# io9.net
KiCad netlist of a schematic drawn in Altium Designer
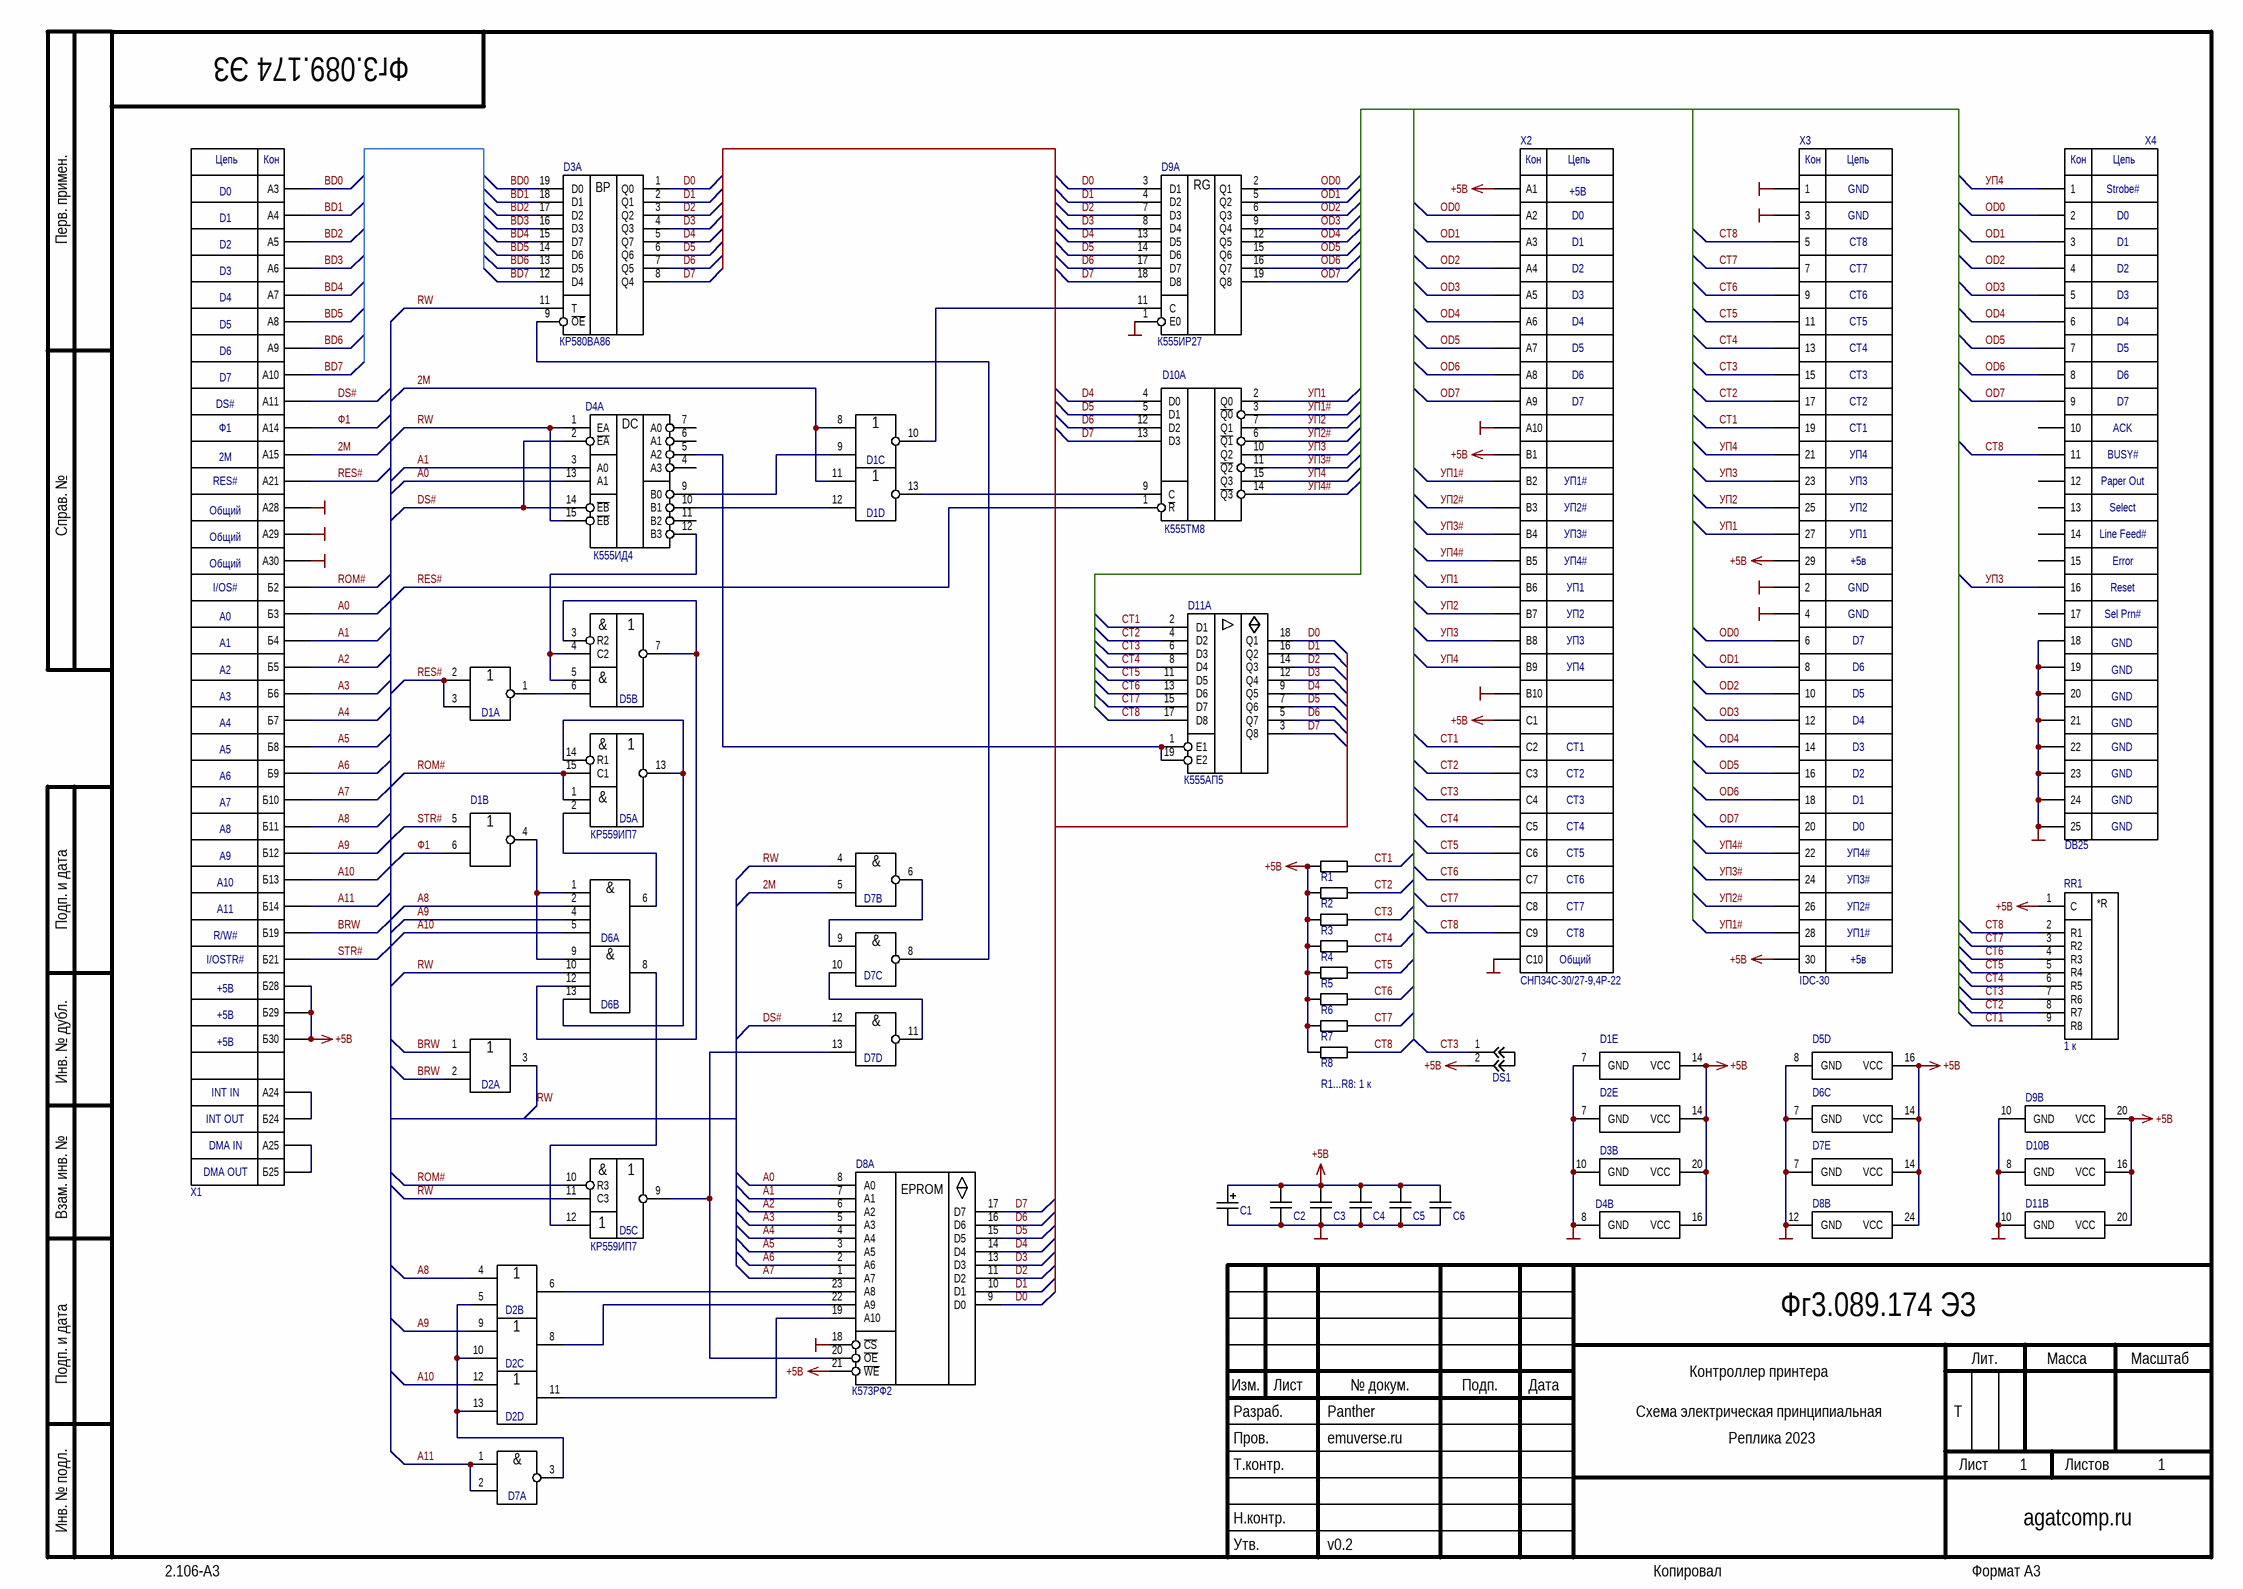
[diagram p0: io9.SchDoc]

(export (version "E")
  (design (tool "Eeschema 10.0.6"))
  (components
    (comp (ref "C1")
      (value "47,0 х 16 в")
      (footprint "CP30")
      (description "К53-14")
      (libsource (lib "Agat") (part "К53-14"))
    )
    (comp (ref "C2")
      (value "0,1 мкф")
      (footprint "C5")
      (description "К10-17")
      (libsource (lib "Agat") (part "К10-17"))
    )
    (comp (ref "C3")
      (value "0,1 мкф")
      (footprint "C5")
      (description "К10-17")
      (libsource (lib "Agat") (part "К10-17"))
    )
    (comp (ref "C4")
      (value "0,1 мкф")
      (footprint "C5")
      (description "К10-17")
      (libsource (lib "Agat") (part "К10-17"))
    )
    (comp (ref "C5")
      (value "0,1 мкф")
      (footprint "C5")
      (description "К10-17")
      (libsource (lib "Agat") (part "К10-17"))
    )
    (comp (ref "C6")
      (value "0,1 мкф")
      (footprint "C5")
      (description "К10-17")
      (libsource (lib "Agat") (part "К10-17"))
    )
    (comp (ref "D1")
      (value "К555ЛЕ1")
      (footprint "201.14")
      (fields (field (name "MANUFACTURERPARTNUMBER") "К555ЛА3"))
      (libsource (lib "Agat") (part "К555ЛЕ1"))
    )
    (comp (ref "D2")
      (value "К555ЛЛ1")
      (footprint "201.14")
      (fields (field (name "MANUFACTURERPARTNUMBER") "К555ЛА3"))
      (libsource (lib "Agat") (part "К555ЛЛ1"))
    )
    (comp (ref "D3") (value "КР580ВА86") (footprint "2140.20") (libsource (lib "Agat") (part "КР580ВА86")))
    (comp (ref "D4") (value "К555ИД4") (footprint "201.16") (libsource (lib "Agat") (part "К555ИД4")))
    (comp (ref "D5")
      (value "КР559ИП7")
      (footprint "201.16")
      (fields (field (name "MANUFACTURERPARTNUMBER") "К555ЛА3"))
      (libsource (lib "Agat") (part "КР559ИП7"))
    )
    (comp (ref "D6")
      (value "К555ЛИ6")
      (footprint "201.14")
      (fields (field (name "MANUFACTURERPARTNUMBER") "К555ЛА3"))
      (libsource (lib "Agat") (part "К555ЛИ6"))
    )
    (comp (ref "D7") (value "К555ЛА3") (footprint "201.14") (libsource (lib "Agat") (part "К555ЛА3")))
    (comp (ref "D8") (value "К573РФ2") (footprint "2120.24 socket") (libsource (lib "Agat") (part "К573РФ2")))
    (comp (ref "D9") (value "К555ИР27") (footprint "201.20") (libsource (lib "Agat") (part "К555ИР27")))
    (comp (ref "D10") (value "К555ТМ8") (footprint "201.16") (libsource (lib "Agat") (part "К555ТМ8")))
    (comp (ref "D11") (value "К555АП5") (footprint "201.20") (libsource (lib "Agat") (part "К555АП5")))
    (comp (ref "DS1")
      (value "HEADER_2x1")
      (footprint "HEADER_2x1")
      (libsource (lib "Agat") (part "HEADER_2x1"))
    )
    (comp (ref "R1")
      (value "1 к")
      (footprint "R10")
      (description "Резистор")
      (libsource (lib "Agat") (part "С2-23"))
    )
    (comp (ref "R2")
      (value "1 к")
      (footprint "R10")
      (description "Резистор")
      (libsource (lib "Agat") (part "С2-23"))
    )
    (comp (ref "R3")
      (value "1 к")
      (footprint "R10")
      (description "Резистор")
      (libsource (lib "Agat") (part "С2-23"))
    )
    (comp (ref "R4")
      (value "1 к")
      (footprint "R10")
      (description "Резистор")
      (libsource (lib "Agat") (part "С2-23"))
    )
    (comp (ref "R5")
      (value "1 к")
      (footprint "R10")
      (description "Резистор")
      (libsource (lib "Agat") (part "С2-23"))
    )
    (comp (ref "R6")
      (value "1 к")
      (footprint "R10")
      (description "Резистор")
      (libsource (lib "Agat") (part "С2-23"))
    )
    (comp (ref "R7")
      (value "1 к")
      (footprint "R10")
      (description "Резистор")
      (libsource (lib "Agat") (part "С2-23"))
    )
    (comp (ref "R8")
      (value "1 к")
      (footprint "R10")
      (description "Резистор")
      (libsource (lib "Agat") (part "С2-23"))
    )
    (comp (ref "RR1")
      (value "1 к")
      (footprint "НР1-4-8")
      (fields (field (name "MANUFACTURERPARTNUMBER") "НР1-4-8"))
      (libsource (lib "Agat") (part "НР1-4-8"))
    )
    (comp (ref "X1")
      (value "Agat-Ext-io9")
      (footprint "AGAT_EXT")
      (libsource (lib "Agat") (part "Agat-Ext-io9"))
    )
    (comp (ref "X2")
      (value "СНП34С-30/27-9,4Р-22")
      (footprint "СНП34-300/27х9,4Р-22-Р")
      (libsource (lib "Agat") (part "IO9_OUT"))
    )
    (comp (ref "X3") (value "IDC-30") (footprint "IDC30") (libsource (lib "Agat") (part "IO9_IDC30")))
    (comp (ref "X4") (value "DB25") (footprint "DB25") (libsource (lib "Agat") (part "DB25_LPT")))
  )
  (nets
    (net (code "1") (name "+5В") (class "Default")
      (node (ref "C1") (pin "1") (pintype "passive"))
      (node (ref "C2") (pin "2") (pintype "passive"))
      (node (ref "C3") (pin "2") (pintype "passive"))
      (node (ref "C4") (pin "2") (pintype "passive"))
      (node (ref "C5") (pin "2") (pintype "passive"))
      (node (ref "C6") (pin "2") (pintype "passive"))
      (node (ref "D1") (pin "14") (pinfunction "VCC_14") (pintype "passive"))
      (node (ref "D10") (pin "16") (pinfunction "VCC_16") (pintype "passive"))
      (node (ref "D11") (pin "20") (pinfunction "VCC_20") (pintype "passive"))
      (node (ref "D2") (pin "14") (pinfunction "VCC_14") (pintype "passive"))
      (node (ref "D3") (pin "20") (pinfunction "VCC_20") (pintype "passive"))
      (node (ref "D4") (pin "16") (pinfunction "VCC_16") (pintype "passive"))
      (node (ref "D5") (pin "16") (pinfunction "VCC_16") (pintype "passive"))
      (node (ref "D6") (pin "14") (pinfunction "VCC_14") (pintype "passive"))
      (node (ref "D7") (pin "14") (pinfunction "VCC_14") (pintype "passive"))
      (node (ref "D8") (pin "21") (pinfunction "~{WE}_21") (pintype "passive"))
      (node (ref "D8") (pin "24") (pinfunction "VCC_24") (pintype "passive"))
      (node (ref "D9") (pin "20") (pinfunction "VCC_20") (pintype "passive"))
      (node (ref "DS1") (pin "2") (pinfunction "2_2") (pintype "passive"))
      (node (ref "R1") (pin "2") (pinfunction "2_2") (pintype "passive"))
      (node (ref "R2") (pin "2") (pinfunction "2_2") (pintype "passive"))
      (node (ref "R3") (pin "2") (pinfunction "2_2") (pintype "passive"))
      (node (ref "R4") (pin "2") (pinfunction "2_2") (pintype "passive"))
      (node (ref "R5") (pin "2") (pinfunction "2_2") (pintype "passive"))
      (node (ref "R6") (pin "2") (pinfunction "2_2") (pintype "passive"))
      (node (ref "R7") (pin "2") (pinfunction "2_2") (pintype "passive"))
      (node (ref "R8") (pin "2") (pinfunction "2_2") (pintype "passive"))
      (node (ref "RR1") (pin "1") (pinfunction "С_1") (pintype "passive"))
      (node (ref "X1") (pin "B28") (pinfunction "Б28_B28") (pintype "passive"))
      (node (ref "X1") (pin "B29") (pinfunction "Б29_B29") (pintype "passive"))
      (node (ref "X1") (pin "B30") (pinfunction "Б30_B30") (pintype "passive"))
      (node (ref "X2") (pin "A1") (pinfunction "A1_A1") (pintype "passive"))
      (node (ref "X2") (pin "B1") (pinfunction "B1_B1") (pintype "passive"))
      (node (ref "X2") (pin "C1") (pinfunction "C1_C1") (pintype "passive"))
      (node (ref "X3") (pin "29") (pinfunction "29_29") (pintype "passive"))
      (node (ref "X3") (pin "30") (pinfunction "30_30") (pintype "passive"))
    )
    (net (code "2") (name "/2M") (class "Default")
      (node (ref "D1") (pin "11") (pinfunction "A_11") (pintype "passive"))
      (node (ref "D1") (pin "8") (pinfunction "A_8") (pintype "passive"))
      (node (ref "D7") (pin "5") (pinfunction "B_5") (pintype "passive"))
      (node (ref "X1") (pin "A15") (pinfunction "A15_A15") (pintype "passive"))
    )
    (net (code "3") (name "/A0") (class "Default")
      (node (ref "D4") (pin "13") (pinfunction "A1_13") (pintype "passive"))
      (node (ref "D8") (pin "8") (pinfunction "A0_8") (pintype "passive"))
      (node (ref "X1") (pin "B3") (pinfunction "Б3_B3") (pintype "passive"))
    )
    (net (code "4") (name "/A1") (class "Default")
      (node (ref "D4") (pin "3") (pinfunction "A0_3") (pintype "passive"))
      (node (ref "D8") (pin "7") (pinfunction "A1_7") (pintype "passive"))
      (node (ref "X1") (pin "B4") (pinfunction "Б4_B4") (pintype "passive"))
    )
    (net (code "5") (name "/A2") (class "Default")
      (node (ref "D8") (pin "6") (pinfunction "A2_6") (pintype "passive"))
      (node (ref "X1") (pin "B5") (pinfunction "Б5_B5") (pintype "passive"))
    )
    (net (code "6") (name "/A3") (class "Default")
      (node (ref "D8") (pin "5") (pinfunction "A3_5") (pintype "passive"))
      (node (ref "X1") (pin "B6") (pinfunction "Б6_B6") (pintype "passive"))
    )
    (net (code "7") (name "/A4") (class "Default")
      (node (ref "D8") (pin "4") (pinfunction "A4_4") (pintype "passive"))
      (node (ref "X1") (pin "B7") (pinfunction "Б7_B7") (pintype "passive"))
    )
    (net (code "8") (name "/A5") (class "Default")
      (node (ref "D8") (pin "3") (pinfunction "A5_3") (pintype "passive"))
      (node (ref "X1") (pin "B8") (pinfunction "Б8_B8") (pintype "passive"))
    )
    (net (code "9") (name "/A6") (class "Default")
      (node (ref "D8") (pin "2") (pinfunction "A6_2") (pintype "passive"))
      (node (ref "X1") (pin "B9") (pinfunction "Б9_B9") (pintype "passive"))
    )
    (net (code "10") (name "/A7") (class "Default")
      (node (ref "D8") (pin "1") (pinfunction "A7_1") (pintype "passive"))
      (node (ref "X1") (pin "B10") (pinfunction "Б10_B10") (pintype "passive"))
    )
    (net (code "11") (name "/A8") (class "Default")
      (node (ref "D2") (pin "4") (pinfunction "A_4") (pintype "passive"))
      (node (ref "D6") (pin "2") (pinfunction "B_2") (pintype "passive"))
      (node (ref "X1") (pin "B11") (pinfunction "Б11_B11") (pintype "passive"))
    )
    (net (code "12") (name "/A9") (class "Default")
      (node (ref "D2") (pin "9") (pinfunction "A_9") (pintype "passive"))
      (node (ref "D6") (pin "4") (pinfunction "C_4") (pintype "passive"))
      (node (ref "X1") (pin "B12") (pinfunction "Б12_B12") (pintype "passive"))
    )
    (net (code "13") (name "/A10") (class "Default")
      (node (ref "D2") (pin "12") (pinfunction "A_12") (pintype "passive"))
      (node (ref "D6") (pin "5") (pinfunction "В_5") (pintype "passive"))
      (node (ref "X1") (pin "B13") (pinfunction "Б13_B13") (pintype "passive"))
    )
    (net (code "14") (name "/A11") (class "Default")
      (node (ref "D7") (pin "1") (pinfunction "A_1") (pintype "passive"))
      (node (ref "D7") (pin "2") (pinfunction "B_2") (pintype "passive"))
      (node (ref "X1") (pin "B14") (pinfunction "Б14_B14") (pintype "passive"))
    )
    (net (code "15") (name "/BD0") (class "Default")
      (node (ref "D3") (pin "19") (pinfunction "D0_19") (pintype "passive"))
      (node (ref "X1") (pin "A3") (pinfunction "A3_A3") (pintype "passive"))
    )
    (net (code "16") (name "/BD1") (class "Default")
      (node (ref "D3") (pin "18") (pinfunction "D1_18") (pintype "passive"))
      (node (ref "X1") (pin "A4") (pinfunction "A4_A4") (pintype "passive"))
    )
    (net (code "17") (name "/BD2") (class "Default")
      (node (ref "D3") (pin "17") (pinfunction "D2_17") (pintype "passive"))
      (node (ref "X1") (pin "A5") (pinfunction "A5_A5") (pintype "passive"))
    )
    (net (code "18") (name "/BD3") (class "Default")
      (node (ref "D3") (pin "16") (pinfunction "D3_16") (pintype "passive"))
      (node (ref "X1") (pin "A6") (pinfunction "A6_A6") (pintype "passive"))
    )
    (net (code "19") (name "/BD4") (class "Default")
      (node (ref "D3") (pin "15") (pinfunction "D7_15") (pintype "passive"))
      (node (ref "X1") (pin "A7") (pinfunction "A7_A7") (pintype "passive"))
    )
    (net (code "20") (name "/BD5") (class "Default")
      (node (ref "D3") (pin "14") (pinfunction "D6_14") (pintype "passive"))
      (node (ref "X1") (pin "A8") (pinfunction "A8_A8") (pintype "passive"))
    )
    (net (code "21") (name "/BD6") (class "Default")
      (node (ref "D3") (pin "13") (pinfunction "D5_13") (pintype "passive"))
      (node (ref "X1") (pin "A9") (pinfunction "A9_A9") (pintype "passive"))
    )
    (net (code "22") (name "/BD7") (class "Default")
      (node (ref "D3") (pin "12") (pinfunction "D4_12") (pintype "passive"))
      (node (ref "X1") (pin "A10") (pinfunction "A10_A10") (pintype "passive"))
    )
    (net (code "23") (name "/BRW") (class "Default")
      (node (ref "D2") (pin "1") (pinfunction "A_1") (pintype "passive"))
      (node (ref "D2") (pin "2") (pinfunction "B_2") (pintype "passive"))
      (node (ref "X1") (pin "B19") (pinfunction "Б19_B19") (pintype "passive"))
    )
    (net (code "24") (name "/CT1") (class "Default")
      (node (ref "D11") (pin "2") (pinfunction "D1_2") (pintype "passive"))
      (node (ref "R1") (pin "1") (pinfunction "1_1") (pintype "passive"))
      (node (ref "RR1") (pin "9") (pinfunction "R8_9") (pintype "passive"))
      (node (ref "X2") (pin "C2") (pinfunction "C2_C2") (pintype "passive"))
      (node (ref "X3") (pin "19") (pinfunction "19_19") (pintype "passive"))
    )
    (net (code "25") (name "/CT2") (class "Default")
      (node (ref "D11") (pin "4") (pinfunction "D2_4") (pintype "passive"))
      (node (ref "R2") (pin "1") (pinfunction "1_1") (pintype "passive"))
      (node (ref "RR1") (pin "8") (pinfunction "R7_8") (pintype "passive"))
      (node (ref "X2") (pin "C3") (pinfunction "C3_C3") (pintype "passive"))
      (node (ref "X3") (pin "17") (pinfunction "17_17") (pintype "passive"))
    )
    (net (code "26") (name "/CT3") (class "Default")
      (node (ref "D11") (pin "6") (pinfunction "D3_6") (pintype "passive"))
      (node (ref "DS1") (pin "1") (pinfunction "1_1") (pintype "passive"))
      (node (ref "R3") (pin "1") (pinfunction "1_1") (pintype "passive"))
      (node (ref "RR1") (pin "7") (pinfunction "R6_7") (pintype "passive"))
      (node (ref "X2") (pin "C4") (pinfunction "C4_C4") (pintype "passive"))
      (node (ref "X3") (pin "15") (pinfunction "15_15") (pintype "passive"))
    )
    (net (code "27") (name "/CT4") (class "Default")
      (node (ref "D11") (pin "8") (pinfunction "D4_8") (pintype "passive"))
      (node (ref "R4") (pin "1") (pinfunction "1_1") (pintype "passive"))
      (node (ref "RR1") (pin "6") (pinfunction "R5_6") (pintype "passive"))
      (node (ref "X2") (pin "C5") (pinfunction "C5_C5") (pintype "passive"))
      (node (ref "X3") (pin "13") (pinfunction "13_13") (pintype "passive"))
    )
    (net (code "28") (name "/CT5") (class "Default")
      (node (ref "D11") (pin "11") (pinfunction "D5_11") (pintype "passive"))
      (node (ref "R5") (pin "1") (pinfunction "1_1") (pintype "passive"))
      (node (ref "RR1") (pin "5") (pinfunction "R4_5") (pintype "passive"))
      (node (ref "X2") (pin "C6") (pinfunction "C6_C6") (pintype "passive"))
      (node (ref "X3") (pin "11") (pinfunction "11_11") (pintype "passive"))
    )
    (net (code "29") (name "/CT6") (class "Default")
      (node (ref "D11") (pin "13") (pinfunction "D6_13") (pintype "passive"))
      (node (ref "R6") (pin "1") (pinfunction "1_1") (pintype "passive"))
      (node (ref "RR1") (pin "4") (pinfunction "R3_4") (pintype "passive"))
      (node (ref "X2") (pin "C7") (pinfunction "C7_C7") (pintype "passive"))
      (node (ref "X3") (pin "9") (pinfunction "9_9") (pintype "passive"))
    )
    (net (code "30") (name "/CT7") (class "Default")
      (node (ref "D11") (pin "15") (pinfunction "D7_15") (pintype "passive"))
      (node (ref "R7") (pin "1") (pinfunction "1_1") (pintype "passive"))
      (node (ref "RR1") (pin "3") (pinfunction "R2_3") (pintype "passive"))
      (node (ref "X2") (pin "C8") (pinfunction "C8_C8") (pintype "passive"))
      (node (ref "X3") (pin "7") (pinfunction "7_7") (pintype "passive"))
    )
    (net (code "31") (name "/CT8") (class "Default")
      (node (ref "D11") (pin "17") (pinfunction "D8_17") (pintype "passive"))
      (node (ref "R8") (pin "1") (pinfunction "1_1") (pintype "passive"))
      (node (ref "RR1") (pin "2") (pinfunction "R1_2") (pintype "passive"))
      (node (ref "X2") (pin "C9") (pinfunction "C9_C9") (pintype "passive"))
      (node (ref "X3") (pin "5") (pinfunction "5_5") (pintype "passive"))
      (node (ref "X4") (pin "11") (pinfunction "11_11") (pintype "passive"))
    )
    (net (code "32") (name "/D0") (class "Default")
      (node (ref "D11") (pin "18") (pinfunction "Q1_18") (pintype "passive"))
      (node (ref "D3") (pin "1") (pinfunction "Q0_1") (pintype "passive"))
      (node (ref "D8") (pin "9") (pinfunction "D0_9") (pintype "passive"))
      (node (ref "D9") (pin "3") (pinfunction "D1_3") (pintype "passive"))
    )
    (net (code "33") (name "/D1") (class "Default")
      (node (ref "D11") (pin "16") (pinfunction "Q2_16") (pintype "passive"))
      (node (ref "D3") (pin "2") (pinfunction "Q1_2") (pintype "passive"))
      (node (ref "D8") (pin "10") (pinfunction "D1_10") (pintype "passive"))
      (node (ref "D9") (pin "4") (pinfunction "D2_4") (pintype "passive"))
    )
    (net (code "34") (name "/D2") (class "Default")
      (node (ref "D11") (pin "14") (pinfunction "Q3_14") (pintype "passive"))
      (node (ref "D3") (pin "3") (pinfunction "Q2_3") (pintype "passive"))
      (node (ref "D8") (pin "11") (pinfunction "D2_11") (pintype "passive"))
      (node (ref "D9") (pin "7") (pinfunction "D3_7") (pintype "passive"))
    )
    (net (code "35") (name "/D3") (class "Default")
      (node (ref "D11") (pin "12") (pinfunction "Q4_12") (pintype "passive"))
      (node (ref "D3") (pin "4") (pinfunction "Q3_4") (pintype "passive"))
      (node (ref "D8") (pin "13") (pinfunction "D3_13") (pintype "passive"))
      (node (ref "D9") (pin "8") (pinfunction "D4_8") (pintype "passive"))
    )
    (net (code "36") (name "/D4") (class "Default")
      (node (ref "D10") (pin "4") (pinfunction "D0_4") (pintype "passive"))
      (node (ref "D11") (pin "9") (pinfunction "Q5_9") (pintype "passive"))
      (node (ref "D3") (pin "5") (pinfunction "Q7_5") (pintype "passive"))
      (node (ref "D8") (pin "14") (pinfunction "D4_14") (pintype "passive"))
      (node (ref "D9") (pin "13") (pinfunction "D5_13") (pintype "passive"))
    )
    (net (code "37") (name "/D5") (class "Default")
      (node (ref "D10") (pin "5") (pinfunction "D1_5") (pintype "passive"))
      (node (ref "D11") (pin "7") (pinfunction "Q6_7") (pintype "passive"))
      (node (ref "D3") (pin "6") (pinfunction "Q6_6") (pintype "passive"))
      (node (ref "D8") (pin "15") (pinfunction "D5_15") (pintype "passive"))
      (node (ref "D9") (pin "14") (pinfunction "D6_14") (pintype "passive"))
    )
    (net (code "38") (name "/D6") (class "Default")
      (node (ref "D10") (pin "12") (pinfunction "D2_12") (pintype "passive"))
      (node (ref "D11") (pin "5") (pinfunction "Q7_5") (pintype "passive"))
      (node (ref "D3") (pin "7") (pinfunction "Q5_7") (pintype "passive"))
      (node (ref "D8") (pin "16") (pinfunction "D6_16") (pintype "passive"))
      (node (ref "D9") (pin "17") (pinfunction "D7_17") (pintype "passive"))
    )
    (net (code "39") (name "/D7") (class "Default")
      (node (ref "D10") (pin "13") (pinfunction "D3_13") (pintype "passive"))
      (node (ref "D11") (pin "3") (pinfunction "Q8_3") (pintype "passive"))
      (node (ref "D3") (pin "8") (pinfunction "Q4_8") (pintype "passive"))
      (node (ref "D8") (pin "17") (pinfunction "D7_17") (pintype "passive"))
      (node (ref "D9") (pin "18") (pinfunction "D8_18") (pintype "passive"))
    )
    (net (code "40") (name "/DS#") (class "Default")
      (node (ref "D4") (pin "14") (pinfunction "~{EB}_14") (pintype "passive"))
      (node (ref "D4") (pin "2") (pinfunction "~{EA}_2") (pintype "passive"))
      (node (ref "D7") (pin "12") (pinfunction "A_12") (pintype "passive"))
      (node (ref "X1") (pin "A11") (pinfunction "A11_A11") (pintype "passive"))
    )
    (net (code "41") (name "/OD0") (class "Default")
      (node (ref "D9") (pin "2") (pinfunction "Q1_2") (pintype "passive"))
      (node (ref "X2") (pin "A2") (pinfunction "A2_A2") (pintype "passive"))
      (node (ref "X3") (pin "6") (pinfunction "6_6") (pintype "passive"))
      (node (ref "X4") (pin "2") (pinfunction "2_2") (pintype "passive"))
    )
    (net (code "42") (name "/OD1") (class "Default")
      (node (ref "D9") (pin "5") (pinfunction "Q2_5") (pintype "passive"))
      (node (ref "X2") (pin "A3") (pinfunction "A3_A3") (pintype "passive"))
      (node (ref "X3") (pin "8") (pinfunction "8_8") (pintype "passive"))
      (node (ref "X4") (pin "3") (pinfunction "3_3") (pintype "passive"))
    )
    (net (code "43") (name "/OD2") (class "Default")
      (node (ref "D9") (pin "6") (pinfunction "Q3_6") (pintype "passive"))
      (node (ref "X2") (pin "A4") (pinfunction "A4_A4") (pintype "passive"))
      (node (ref "X3") (pin "10") (pinfunction "10_10") (pintype "passive"))
      (node (ref "X4") (pin "4") (pinfunction "4_4") (pintype "passive"))
    )
    (net (code "44") (name "/OD3") (class "Default")
      (node (ref "D9") (pin "9") (pinfunction "Q4_9") (pintype "passive"))
      (node (ref "X2") (pin "A5") (pinfunction "A5_A5") (pintype "passive"))
      (node (ref "X3") (pin "12") (pinfunction "12_12") (pintype "passive"))
      (node (ref "X4") (pin "5") (pinfunction "5_5") (pintype "passive"))
    )
    (net (code "45") (name "/OD4") (class "Default")
      (node (ref "D9") (pin "12") (pinfunction "Q5_12") (pintype "passive"))
      (node (ref "X2") (pin "A6") (pinfunction "A6_A6") (pintype "passive"))
      (node (ref "X3") (pin "14") (pinfunction "14_14") (pintype "passive"))
      (node (ref "X4") (pin "6") (pinfunction "6_6") (pintype "passive"))
    )
    (net (code "46") (name "/OD5") (class "Default")
      (node (ref "D9") (pin "15") (pinfunction "Q6_15") (pintype "passive"))
      (node (ref "X2") (pin "A7") (pinfunction "A7_A7") (pintype "passive"))
      (node (ref "X3") (pin "16") (pinfunction "16_16") (pintype "passive"))
      (node (ref "X4") (pin "7") (pinfunction "7_7") (pintype "passive"))
    )
    (net (code "47") (name "/OD6") (class "Default")
      (node (ref "D9") (pin "16") (pinfunction "Q7_16") (pintype "passive"))
      (node (ref "X2") (pin "A8") (pinfunction "A8_A8") (pintype "passive"))
      (node (ref "X3") (pin "18") (pinfunction "18_18") (pintype "passive"))
      (node (ref "X4") (pin "8") (pinfunction "8_8") (pintype "passive"))
    )
    (net (code "48") (name "/OD7") (class "Default")
      (node (ref "D9") (pin "19") (pinfunction "Q8_19") (pintype "passive"))
      (node (ref "X2") (pin "A9") (pinfunction "A9_A9") (pintype "passive"))
      (node (ref "X3") (pin "20") (pinfunction "20_20") (pintype "passive"))
      (node (ref "X4") (pin "9") (pinfunction "9_9") (pintype "passive"))
    )
    (net (code "49") (name "/RES#") (class "Default")
      (node (ref "D1") (pin "2") (pinfunction "A_2") (pintype "passive"))
      (node (ref "D1") (pin "3") (pinfunction "B_3") (pintype "passive"))
      (node (ref "D10") (pin "1") (pinfunction "~{R}_1") (pintype "passive"))
      (node (ref "X1") (pin "A21") (pinfunction "A21_A21") (pintype "passive"))
    )
    (net (code "50") (name "/ROM#") (class "Default")
      (node (ref "D5") (pin "1") (pinfunction "A_1") (pintype "passive"))
      (node (ref "D5") (pin "10") (pinfunction "R3_10") (pintype "passive"))
      (node (ref "D5") (pin "15") (pinfunction "C1_15") (pintype "passive"))
      (node (ref "X1") (pin "B2") (pinfunction "Б2_B2") (pintype "passive"))
    )
    (net (code "51") (name "/RW") (class "Default")
      (node (ref "D2") (pin "3") (pinfunction "~{O}_3") (pintype "passive"))
      (node (ref "D3") (pin "11") (pinfunction "T_11") (pintype "passive"))
      (node (ref "D4") (pin "1") (pinfunction "EA_1") (pintype "passive"))
      (node (ref "D4") (pin "15") (pinfunction "~{EB}_15") (pintype "passive"))
      (node (ref "D5") (pin "11") (pinfunction "C3_11") (pintype "passive"))
      (node (ref "D6") (pin "10") (pinfunction "B_10") (pintype "passive"))
      (node (ref "D7") (pin "4") (pinfunction "A_4") (pintype "passive"))
    )
    (net (code "52") (name "/STR#") (class "Default")
      (node (ref "D1") (pin "5") (pinfunction "A_5") (pintype "passive"))
      (node (ref "X1") (pin "B21") (pinfunction "Б21_B21") (pintype "passive"))
    )
    (net (code "53") (name "/УП1") (class "Default")
      (node (ref "D10") (pin "2") (pinfunction "Q0_2") (pintype "passive"))
      (node (ref "X2") (pin "B6") (pinfunction "B6_B6") (pintype "passive"))
      (node (ref "X3") (pin "27") (pinfunction "27_27") (pintype "passive"))
    )
    (net (code "54") (name "/УП1#") (class "Default")
      (node (ref "D10") (pin "3") (pinfunction "~{Q0}_3") (pintype "passive"))
      (node (ref "X2") (pin "B2") (pinfunction "B2_B2") (pintype "passive"))
      (node (ref "X3") (pin "28") (pinfunction "28_28") (pintype "passive"))
    )
    (net (code "55") (name "/УП2") (class "Default")
      (node (ref "D10") (pin "7") (pinfunction "Q1_7") (pintype "passive"))
      (node (ref "X2") (pin "B7") (pinfunction "B7_B7") (pintype "passive"))
      (node (ref "X3") (pin "25") (pinfunction "25_25") (pintype "passive"))
    )
    (net (code "56") (name "/УП2#") (class "Default")
      (node (ref "D10") (pin "6") (pinfunction "~{Q1}_6") (pintype "passive"))
      (node (ref "X2") (pin "B3") (pinfunction "B3_B3") (pintype "passive"))
      (node (ref "X3") (pin "26") (pinfunction "26_26") (pintype "passive"))
    )
    (net (code "57") (name "/УП3") (class "Default")
      (node (ref "D10") (pin "10") (pinfunction "Q2_10") (pintype "passive"))
      (node (ref "X2") (pin "B8") (pinfunction "B8_B8") (pintype "passive"))
      (node (ref "X3") (pin "23") (pinfunction "23_23") (pintype "passive"))
      (node (ref "X4") (pin "16") (pinfunction "16_16") (pintype "passive"))
    )
    (net (code "58") (name "/УП3#") (class "Default")
      (node (ref "D10") (pin "11") (pinfunction "~{Q2}_11") (pintype "passive"))
      (node (ref "X2") (pin "B4") (pinfunction "B4_B4") (pintype "passive"))
      (node (ref "X3") (pin "24") (pinfunction "24_24") (pintype "passive"))
    )
    (net (code "59") (name "/УП4") (class "Default")
      (node (ref "D10") (pin "15") (pinfunction "Q3_15") (pintype "passive"))
      (node (ref "X2") (pin "B9") (pinfunction "B9_B9") (pintype "passive"))
      (node (ref "X3") (pin "21") (pinfunction "21_21") (pintype "passive"))
      (node (ref "X4") (pin "1") (pinfunction "1_1") (pintype "passive"))
    )
    (net (code "60") (name "/УП4#") (class "Default")
      (node (ref "D10") (pin "14") (pinfunction "~{Q3}_14") (pintype "passive"))
      (node (ref "X2") (pin "B5") (pinfunction "B5_B5") (pintype "passive"))
      (node (ref "X3") (pin "22") (pinfunction "22_22") (pintype "passive"))
    )
    (net (code "61") (name "/Ф1") (class "Default")
      (node (ref "D1") (pin "6") (pinfunction "B_6") (pintype "passive"))
      (node (ref "X1") (pin "A14") (pinfunction "A14_A14") (pintype "passive"))
    )
    (net (code "62") (name "GND") (class "Default")
      (node (ref "C1") (pin "2") (pintype "passive"))
      (node (ref "C2") (pin "1") (pintype "passive"))
      (node (ref "C3") (pin "1") (pintype "passive"))
      (node (ref "C4") (pin "1") (pintype "passive"))
      (node (ref "C5") (pin "1") (pintype "passive"))
      (node (ref "C6") (pin "1") (pintype "passive"))
      (node (ref "D1") (pin "7") (pinfunction "GND_7") (pintype "passive"))
      (node (ref "D10") (pin "8") (pinfunction "GND_8") (pintype "passive"))
      (node (ref "D11") (pin "10") (pinfunction "GND_10") (pintype "passive"))
      (node (ref "D2") (pin "7") (pinfunction "GND_7") (pintype "passive"))
      (node (ref "D3") (pin "10") (pinfunction "GND_10") (pintype "passive"))
      (node (ref "D4") (pin "8") (pinfunction "GND_8") (pintype "passive"))
      (node (ref "D5") (pin "8") (pinfunction "GND_8") (pintype "passive"))
      (node (ref "D6") (pin "7") (pinfunction "GND_7") (pintype "passive"))
      (node (ref "D7") (pin "7") (pinfunction "GND_7") (pintype "passive"))
      (node (ref "D8") (pin "12") (pinfunction "GND_12") (pintype "passive"))
      (node (ref "D8") (pin "18") (pinfunction "~{CS}_18") (pintype "passive"))
      (node (ref "D9") (pin "1") (pinfunction "E0_1") (pintype "passive"))
      (node (ref "D9") (pin "10") (pinfunction "GND_10") (pintype "passive"))
      (node (ref "X1") (pin "A28") (pinfunction "A28_A28") (pintype "passive"))
      (node (ref "X1") (pin "A29") (pinfunction "A29_A29") (pintype "passive"))
      (node (ref "X1") (pin "A30") (pinfunction "A30_A30") (pintype "passive"))
      (node (ref "X2") (pin "A10") (pinfunction "A10_A10") (pintype "passive"))
      (node (ref "X2") (pin "B10") (pinfunction "B10_B10") (pintype "passive"))
      (node (ref "X2") (pin "C10") (pinfunction "C10_C10") (pintype "passive"))
      (node (ref "X3") (pin "1") (pinfunction "1_1") (pintype "passive"))
      (node (ref "X3") (pin "2") (pinfunction "2_2") (pintype "passive"))
      (node (ref "X3") (pin "3") (pinfunction "3_3") (pintype "passive"))
      (node (ref "X3") (pin "4") (pinfunction "4_4") (pintype "passive"))
      (node (ref "X4") (pin "18") (pinfunction "18_18") (pintype "passive"))
      (node (ref "X4") (pin "19") (pinfunction "19_19") (pintype "passive"))
      (node (ref "X4") (pin "20") (pinfunction "20_20") (pintype "passive"))
      (node (ref "X4") (pin "21") (pinfunction "21_21") (pintype "passive"))
      (node (ref "X4") (pin "22") (pinfunction "22_22") (pintype "passive"))
      (node (ref "X4") (pin "23") (pinfunction "23_23") (pintype "passive"))
      (node (ref "X4") (pin "24") (pinfunction "24_24") (pintype "passive"))
      (node (ref "X4") (pin "25") (pinfunction "25_25") (pintype "passive"))
    )
    (net (code "63") (name "Net-(D1A-~{O})") (class "Default")
      (node (ref "D1") (pin "1") (pinfunction "~{O}_1") (pintype "passive"))
      (node (ref "D5") (pin "6") (pinfunction "B_6") (pintype "passive"))
    )
    (net (code "64") (name "Net-(D1B-~{O})") (class "Default")
      (node (ref "D1") (pin "4") (pinfunction "~{O}_4") (pintype "passive"))
      (node (ref "D6") (pin "1") (pinfunction "A_1") (pintype "passive"))
      (node (ref "D6") (pin "9") (pinfunction "A_9") (pintype "passive"))
    )
    (net (code "65") (name "Net-(D1C-B)") (class "Default")
      (node (ref "D1") (pin "9") (pinfunction "B_9") (pintype "passive"))
      (node (ref "D4") (pin "9") (pinfunction "B0_9") (pintype "passive"))
    )
    (net (code "66") (name "Net-(D1C-~{O})") (class "Default")
      (node (ref "D1") (pin "10") (pinfunction "~{O}_10") (pintype "passive"))
      (node (ref "D9") (pin "11") (pinfunction "C_11") (pintype "passive"))
    )
    (net (code "67") (name "Net-(D1D-B)") (class "Default")
      (node (ref "D1") (pin "12") (pinfunction "B_12") (pintype "passive"))
      (node (ref "D4") (pin "10") (pinfunction "B1_10") (pintype "passive"))
    )
    (net (code "68") (name "Net-(D2B-B)") (class "Default")
      (node (ref "D2") (pin "10") (pinfunction "B_10") (pintype "passive"))
      (node (ref "D2") (pin "13") (pinfunction "B_13") (pintype "passive"))
      (node (ref "D2") (pin "5") (pinfunction "B_5") (pintype "passive"))
      (node (ref "D7") (pin "3") (pinfunction "~{O}_3") (pintype "passive"))
    )
    (net (code "69") (name "Net-(D2B-~{O})") (class "Default")
      (node (ref "D2") (pin "6") (pinfunction "~{O}_6") (pintype "passive"))
      (node (ref "D8") (pin "23") (pinfunction "A8_23") (pintype "passive"))
    )
    (net (code "70") (name "Net-(D2C-~{O})") (class "Default")
      (node (ref "D2") (pin "8") (pinfunction "~{O}_8") (pintype "passive"))
      (node (ref "D8") (pin "22") (pinfunction "A9_22") (pintype "passive"))
    )
    (net (code "71") (name "Net-(D2D-~{O})") (class "Default")
      (node (ref "D2") (pin "11") (pinfunction "~{O}_11") (pintype "passive"))
      (node (ref "D8") (pin "19") (pinfunction "A10_19") (pintype "passive"))
    )
    (net (code "72") (name "Net-(D3A-~{OE})") (class "Default")
      (node (ref "D3") (pin "9") (pinfunction "~{OE}_9") (pintype "passive"))
      (node (ref "D7") (pin "8") (pinfunction "~{O}_8") (pintype "passive"))
    )
    (net (code "73") (name "Net-(D4A-B3)") (class "Default")
      (node (ref "D4") (pin "12") (pinfunction "B3_12") (pintype "passive"))
      (node (ref "D5") (pin "4") (pinfunction "C2_4") (pintype "passive"))
      (node (ref "D5") (pin "5") (pinfunction "A_5") (pintype "passive"))
    )
    (net (code "74") (name "Net-(D5A-B)") (class "Default")
      (node (ref "D5") (pin "2") (pinfunction "B_2") (pintype "passive"))
      (node (ref "D6") (pin "6") (pinfunction "~{O}_6") (pintype "passive"))
    )
    (net (code "75") (name "Net-(D5A-R1)") (class "Default")
      (node (ref "D5") (pin "13") (pinfunction "~{O}_13") (pintype "passive"))
      (node (ref "D5") (pin "14") (pinfunction "R1_14") (pintype "passive"))
      (node (ref "D6") (pin "13") (pinfunction "D_13") (pintype "passive"))
    )
    (net (code "76") (name "Net-(D5B-R2)") (class "Default")
      (node (ref "D5") (pin "3") (pinfunction "R2_3") (pintype "passive"))
      (node (ref "D5") (pin "7") (pinfunction "~{O}_7") (pintype "passive"))
      (node (ref "D6") (pin "12") (pinfunction "C_12") (pintype "passive"))
    )
    (net (code "77") (name "Net-(D5C-A)") (class "Default")
      (node (ref "D5") (pin "12") (pinfunction "A_12") (pintype "passive"))
      (node (ref "D6") (pin "8") (pinfunction "~{O}_8") (pintype "passive"))
    )
    (net (code "78") (name "Net-(D5C-~{O})") (class "Default")
      (node (ref "D5") (pin "9") (pinfunction "~{O}_9") (pintype "passive"))
      (node (ref "D7") (pin "13") (pinfunction "B_13") (pintype "passive"))
      (node (ref "D8") (pin "20") (pinfunction "~{OE}_20") (pintype "passive"))
    )
    (net (code "79") (name "Net-(D7B-~{O})") (class "Default")
      (node (ref "D7") (pin "6") (pinfunction "~{O}_6") (pintype "passive"))
      (node (ref "D7") (pin "9") (pinfunction "A_9") (pintype "passive"))
    )
    (net (code "80") (name "Net-(D7C-B)") (class "Default")
      (node (ref "D7") (pin "10") (pinfunction "B_10") (pintype "passive"))
      (node (ref "D7") (pin "11") (pinfunction "~{O}_11") (pintype "passive"))
    )
    (net (code "81") (name "Net-(D10A-C)") (class "Default")
      (node (ref "D1") (pin "13") (pinfunction "~{O}_13") (pintype "passive"))
      (node (ref "D10") (pin "9") (pinfunction "C_9") (pintype "passive"))
    )
    (net (code "82") (name "Net-(D11A-E1)") (class "Default")
      (node (ref "D11") (pin "1") (pinfunction "E1_1") (pintype "passive"))
      (node (ref "D11") (pin "19") (pinfunction "E2_19") (pintype "passive"))
      (node (ref "D4") (pin "5") (pinfunction "A2_5") (pintype "passive"))
    )
    (net (code "83") (name "Net-(X1-Б24)") (class "Default")
      (node (ref "X1") (pin "A24") (pinfunction "A24_A24") (pintype "passive"))
      (node (ref "X1") (pin "B24") (pinfunction "Б24_B24") (pintype "passive"))
    )
    (net (code "84") (name "Net-(X1-Б25)") (class "Default")
      (node (ref "X1") (pin "A25") (pinfunction "A25_A25") (pintype "passive"))
      (node (ref "X1") (pin "B25") (pinfunction "Б25_B25") (pintype "passive"))
    )
    (net (code "85") (name "unconnected-(D4A-A0-Pad7)") (class "Default")
      (node (ref "D4") (pin "7") (pinfunction "A0_7") (pintype "passive"))
    )
    (net (code "86") (name "unconnected-(D4A-A1-Pad6)") (class "Default")
      (node (ref "D4") (pin "6") (pinfunction "A1_6") (pintype "passive"))
    )
    (net (code "87") (name "unconnected-(D4A-A3-Pad4)") (class "Default")
      (node (ref "D4") (pin "4") (pinfunction "A3_4") (pintype "passive"))
    )
    (net (code "88") (name "unconnected-(D4A-B2-Pad11)") (class "Default")
      (node (ref "D4") (pin "11") (pinfunction "B2_11") (pintype "passive"))
    )
    (net (code "89") (name "unconnected-(X4-Pad10)") (class "Default")
      (node (ref "X4") (pin "10") (pinfunction "10_10") (pintype "passive"))
    )
    (net (code "90") (name "unconnected-(X4-Pad12)") (class "Default")
      (node (ref "X4") (pin "12") (pinfunction "12_12") (pintype "passive"))
    )
    (net (code "91") (name "unconnected-(X4-Pad13)") (class "Default")
      (node (ref "X4") (pin "13") (pinfunction "13_13") (pintype "passive"))
    )
    (net (code "92") (name "unconnected-(X4-Pad14)") (class "Default")
      (node (ref "X4") (pin "14") (pinfunction "14_14") (pintype "passive"))
    )
    (net (code "93") (name "unconnected-(X4-Pad15)") (class "Default")
      (node (ref "X4") (pin "15") (pinfunction "15_15") (pintype "passive"))
    )
    (net (code "94") (name "unconnected-(X4-Pad17)") (class "Default")
      (node (ref "X4") (pin "17") (pinfunction "17_17") (pintype "passive"))
    )
  )
)
